# M706X.net
KiCad netlist of a schematic drawn in EAGLE
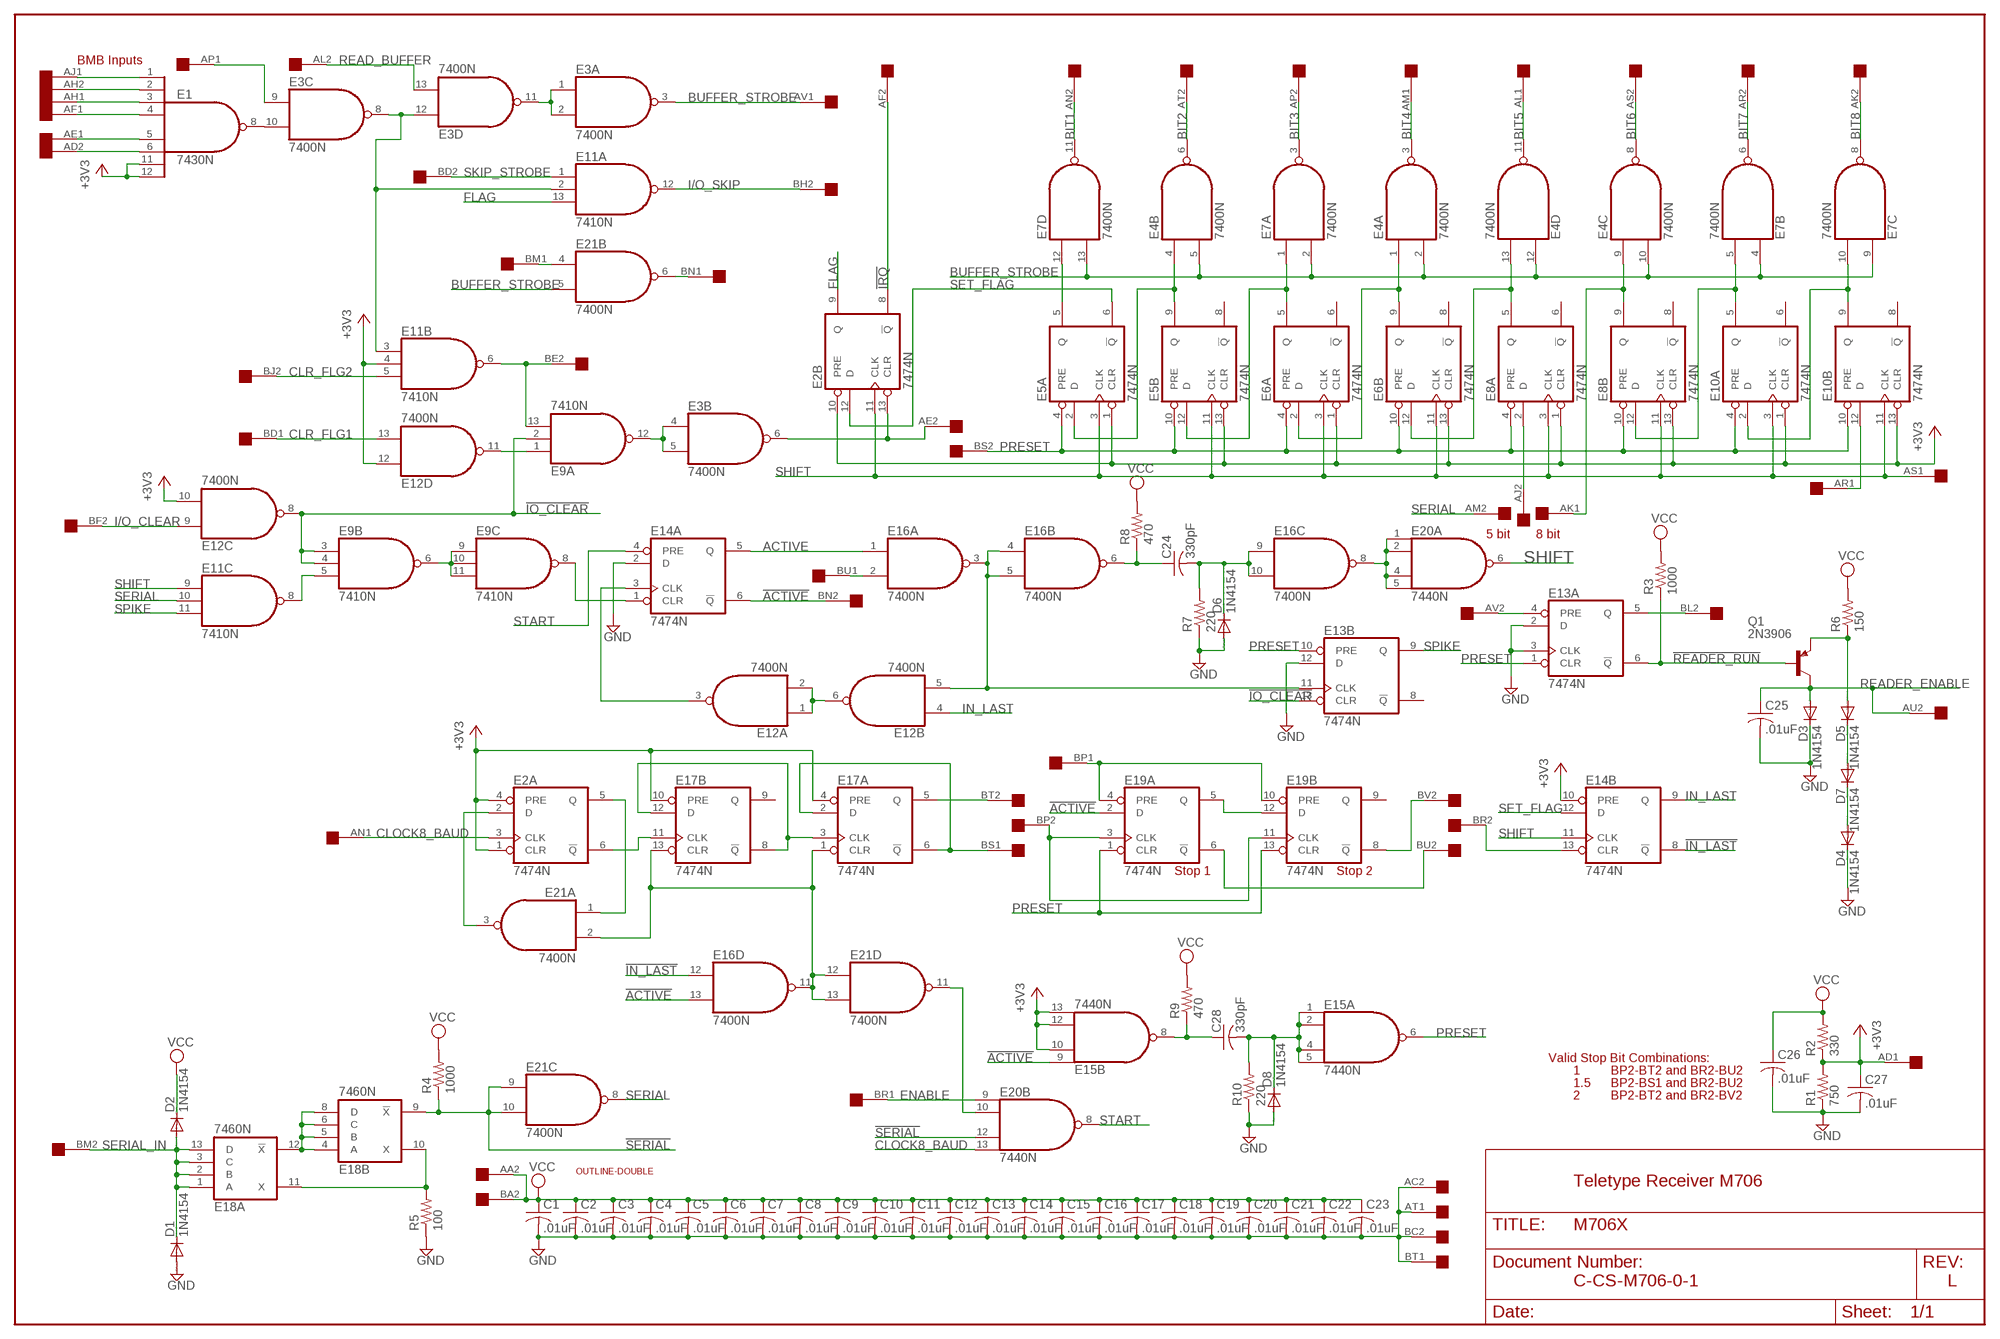
[diagram p0: schematic, sheet 1]

(export (version "E")
  (design (tool "Eeschema 10.0.6"))
  (components
    (comp (ref "C1")
      (value ".01uF")
      (footprint "eagle-import:C050-025X075")
      (libsource (lib "eagle-import") (part "C-US050-025X075"))
    )
    (comp (ref "C2")
      (value ".01uF")
      (footprint "eagle-import:C050-025X075")
      (libsource (lib "eagle-import") (part "C-US050-025X075"))
    )
    (comp (ref "C3")
      (value ".01uF")
      (footprint "eagle-import:C050-025X075")
      (libsource (lib "eagle-import") (part "C-US050-025X075"))
    )
    (comp (ref "C4")
      (value ".01uF")
      (footprint "eagle-import:C050-025X075")
      (libsource (lib "eagle-import") (part "C-US050-025X075"))
    )
    (comp (ref "C5")
      (value ".01uF")
      (footprint "eagle-import:C050-025X075")
      (libsource (lib "eagle-import") (part "C-US050-025X075"))
    )
    (comp (ref "C6")
      (value ".01uF")
      (footprint "eagle-import:C050-025X075")
      (libsource (lib "eagle-import") (part "C-US050-025X075"))
    )
    (comp (ref "C7")
      (value ".01uF")
      (footprint "eagle-import:C050-025X075")
      (libsource (lib "eagle-import") (part "C-US050-025X075"))
    )
    (comp (ref "C8")
      (value ".01uF")
      (footprint "eagle-import:C050-025X075")
      (libsource (lib "eagle-import") (part "C-US050-025X075"))
    )
    (comp (ref "C9")
      (value ".01uF")
      (footprint "eagle-import:C050-025X075")
      (libsource (lib "eagle-import") (part "C-US050-025X075"))
    )
    (comp (ref "C10")
      (value ".01uF")
      (footprint "eagle-import:C050-025X075")
      (libsource (lib "eagle-import") (part "C-US050-025X075"))
    )
    (comp (ref "C11")
      (value ".01uF")
      (footprint "eagle-import:C050-025X075")
      (libsource (lib "eagle-import") (part "C-US050-025X075"))
    )
    (comp (ref "C12")
      (value ".01uF")
      (footprint "eagle-import:C050-025X075")
      (libsource (lib "eagle-import") (part "C-US050-025X075"))
    )
    (comp (ref "C13")
      (value ".01uF")
      (footprint "eagle-import:C050-025X075")
      (libsource (lib "eagle-import") (part "C-US050-025X075"))
    )
    (comp (ref "C14")
      (value ".01uF")
      (footprint "eagle-import:C050-025X075")
      (libsource (lib "eagle-import") (part "C-US050-025X075"))
    )
    (comp (ref "C15")
      (value ".01uF")
      (footprint "eagle-import:C050-025X075")
      (libsource (lib "eagle-import") (part "C-US050-025X075"))
    )
    (comp (ref "C16")
      (value ".01uF")
      (footprint "eagle-import:C050-025X075")
      (libsource (lib "eagle-import") (part "C-US050-025X075"))
    )
    (comp (ref "C17")
      (value ".01uF")
      (footprint "eagle-import:C050-025X075")
      (libsource (lib "eagle-import") (part "C-US050-025X075"))
    )
    (comp (ref "C18")
      (value ".01uF")
      (footprint "eagle-import:C050-025X075")
      (libsource (lib "eagle-import") (part "C-US050-025X075"))
    )
    (comp (ref "C19")
      (value ".01uF")
      (footprint "eagle-import:C050-025X075")
      (libsource (lib "eagle-import") (part "C-US050-025X075"))
    )
    (comp (ref "C20")
      (value ".01uF")
      (footprint "eagle-import:C050-025X075")
      (libsource (lib "eagle-import") (part "C-US050-025X075"))
    )
    (comp (ref "C21")
      (value ".01uF")
      (footprint "eagle-import:C050-025X075")
      (libsource (lib "eagle-import") (part "C-US050-025X075"))
    )
    (comp (ref "C22")
      (value ".01uF")
      (footprint "eagle-import:C050-025X075")
      (libsource (lib "eagle-import") (part "C-US050-025X075"))
    )
    (comp (ref "C23")
      (value ".01uF")
      (footprint "eagle-import:C050-025X075")
      (libsource (lib "eagle-import") (part "C-US050-025X075"))
    )
    (comp (ref "C24")
      (value "330pF")
      (footprint "eagle-import:C050-025X075")
      (libsource (lib "eagle-import") (part "C-US050-025X075"))
    )
    (comp (ref "C25")
      (value ".01uF")
      (footprint "eagle-import:C050-025X075")
      (libsource (lib "eagle-import") (part "C-US050-025X075"))
    )
    (comp (ref "C26")
      (value ".01uF")
      (footprint "eagle-import:C050-025X075")
      (libsource (lib "eagle-import") (part "C-US050-025X075"))
    )
    (comp (ref "C27")
      (value ".01uF")
      (footprint "eagle-import:C050-025X075")
      (libsource (lib "eagle-import") (part "C-US050-025X075"))
    )
    (comp (ref "C28")
      (value "330pF")
      (footprint "eagle-import:C050-025X075")
      (libsource (lib "eagle-import") (part "C-US050-025X075"))
    )
    (comp (ref "D1")
      (value "1N4154")
      (footprint "eagle-import:DO35-10")
      (libsource (lib "eagle-import") (part "1N4148DO35-10"))
    )
    (comp (ref "D2")
      (value "1N4154")
      (footprint "eagle-import:DO35-10")
      (libsource (lib "eagle-import") (part "1N4148DO35-10"))
    )
    (comp (ref "D3")
      (value "1N4154")
      (footprint "eagle-import:DO35-10")
      (libsource (lib "eagle-import") (part "1N4148DO35-10"))
    )
    (comp (ref "D4")
      (value "1N4154")
      (footprint "eagle-import:DO35-10")
      (libsource (lib "eagle-import") (part "1N4148DO35-10"))
    )
    (comp (ref "D5")
      (value "1N4154")
      (footprint "eagle-import:DO35-10")
      (libsource (lib "eagle-import") (part "1N4148DO35-10"))
    )
    (comp (ref "D6")
      (value "1N4154")
      (footprint "eagle-import:DO35-10")
      (libsource (lib "eagle-import") (part "1N4148DO35-10"))
    )
    (comp (ref "D7")
      (value "1N4154")
      (footprint "eagle-import:DO35-10")
      (libsource (lib "eagle-import") (part "1N4148DO35-10"))
    )
    (comp (ref "D8")
      (value "1N4154")
      (footprint "eagle-import:DO35-10")
      (libsource (lib "eagle-import") (part "1N4148DO35-10"))
    )
    (comp (ref "E1")
      (value "7430N")
      (footprint "eagle-import:DIL14")
      (libsource (lib "eagle-import") (part "7430N"))
    )
    (comp (ref "E2")
      (value "7474N")
      (footprint "eagle-import:DIL14")
      (libsource (lib "eagle-import") (part "7474NS"))
    )
    (comp (ref "E3")
      (value "7400N")
      (footprint "eagle-import:DIL14")
      (libsource (lib "eagle-import") (part "7400N"))
    )
    (comp (ref "E4")
      (value "7400N")
      (footprint "eagle-import:DIL14")
      (libsource (lib "eagle-import") (part "7400N"))
    )
    (comp (ref "E5")
      (value "7474N")
      (footprint "eagle-import:DIL14")
      (libsource (lib "eagle-import") (part "7474NS"))
    )
    (comp (ref "E6")
      (value "7474N")
      (footprint "eagle-import:DIL14")
      (libsource (lib "eagle-import") (part "7474NS"))
    )
    (comp (ref "E7")
      (value "7400N")
      (footprint "eagle-import:DIL14")
      (libsource (lib "eagle-import") (part "7400N"))
    )
    (comp (ref "E8")
      (value "7474N")
      (footprint "eagle-import:DIL14")
      (libsource (lib "eagle-import") (part "7474NS"))
    )
    (comp (ref "E9")
      (value "7410N")
      (footprint "eagle-import:DIL14")
      (libsource (lib "eagle-import") (part "7410N"))
    )
    (comp (ref "E10")
      (value "7474N")
      (footprint "eagle-import:DIL14")
      (libsource (lib "eagle-import") (part "7474NS"))
    )
    (comp (ref "E11")
      (value "7410N")
      (footprint "eagle-import:DIL14")
      (libsource (lib "eagle-import") (part "7410N"))
    )
    (comp (ref "E12")
      (value "7400N")
      (footprint "eagle-import:DIL14")
      (libsource (lib "eagle-import") (part "7400N"))
    )
    (comp (ref "E13")
      (value "7474N")
      (footprint "eagle-import:DIL14")
      (libsource (lib "eagle-import") (part "7474NS"))
    )
    (comp (ref "E14")
      (value "7474N")
      (footprint "eagle-import:DIL14")
      (libsource (lib "eagle-import") (part "7474NS"))
    )
    (comp (ref "E15")
      (value "7440N")
      (footprint "eagle-import:DIL14")
      (libsource (lib "eagle-import") (part "7420NS"))
    )
    (comp (ref "E16")
      (value "7400N")
      (footprint "eagle-import:DIL14")
      (libsource (lib "eagle-import") (part "7400N"))
    )
    (comp (ref "E17")
      (value "7474N")
      (footprint "eagle-import:DIL14")
      (libsource (lib "eagle-import") (part "7474NS"))
    )
    (comp (ref "E18")
      (value "7460N")
      (footprint "eagle-import:DIL14")
      (libsource (lib "eagle-import") (part "7460N"))
    )
    (comp (ref "E19")
      (value "7474N")
      (footprint "eagle-import:DIL14")
      (libsource (lib "eagle-import") (part "7474NS"))
    )
    (comp (ref "E20")
      (value "7440N")
      (footprint "eagle-import:DIL14")
      (libsource (lib "eagle-import") (part "7420NS"))
    )
    (comp (ref "E21")
      (value "7400N")
      (footprint "eagle-import:DIL14")
      (libsource (lib "eagle-import") (part "7400N"))
    )
    (comp (ref "Q1")
      (value "2N3906")
      (footprint "eagle-import:TO39")
      (libsource (lib "eagle-import") (part "2N2904"))
    )
    (comp (ref "R1")
      (value "750")
      (footprint "eagle-import:0207_10")
      (libsource (lib "eagle-import") (part "R-US_0207/10"))
    )
    (comp (ref "R2")
      (value "330")
      (footprint "eagle-import:0207_10")
      (libsource (lib "eagle-import") (part "R-US_0207/10"))
    )
    (comp (ref "R3")
      (value "1000")
      (footprint "eagle-import:0207_10")
      (libsource (lib "eagle-import") (part "R-US_0207/10"))
    )
    (comp (ref "R4")
      (value "1000")
      (footprint "eagle-import:0207_10")
      (libsource (lib "eagle-import") (part "R-US_0207/10"))
    )
    (comp (ref "R5")
      (value "100")
      (footprint "eagle-import:0207_10")
      (libsource (lib "eagle-import") (part "R-US_0207/10"))
    )
    (comp (ref "R6")
      (value "150")
      (footprint "eagle-import:0207_10")
      (libsource (lib "eagle-import") (part "R-US_0207/10"))
    )
    (comp (ref "R7")
      (value "220")
      (footprint "eagle-import:0207_10")
      (libsource (lib "eagle-import") (part "R-US_0207/10"))
    )
    (comp (ref "R8")
      (value "470")
      (footprint "eagle-import:0207_10")
      (libsource (lib "eagle-import") (part "R-US_0207/10"))
    )
    (comp (ref "R9")
      (value "470")
      (footprint "eagle-import:0207_10")
      (libsource (lib "eagle-import") (part "R-US_0207/10"))
    )
    (comp (ref "R10")
      (value "220")
      (footprint "eagle-import:0207_10")
      (libsource (lib "eagle-import") (part "R-US_0207/10"))
    )
    (comp (ref "U$1")
      (value "OUTLINE-DOUBLE")
      (footprint "eagle-import:DOUBLE")
      (libsource (lib "eagle-import") (part "OUTLINE-DOUBLE"))
    )
    (comp (ref "U$2")
      (value "DOUBLE")
      (footprint "eagle-import:EDGE-CON4")
      (libsource (lib "eagle-import") (part "DOUBLE"))
    )
  )
  (nets
    (net (code "1") (name "+3V3") (class "Default")
      (node (ref "C27") (pin "1") (pinfunction "1_1") (pintype "passive"))
      (node (ref "E1") (pin "11") (pinfunction "I6_11") (pintype "input"))
      (node (ref "E1") (pin "12") (pinfunction "I7_12") (pintype "input"))
      (node (ref "E10") (pin "1") (pinfunction "CLR_1") (pintype "input"))
      (node (ref "E10") (pin "13") (pinfunction "CLR_13") (pintype "input"))
      (node (ref "E11") (pin "4") (pinfunction "I1_4") (pintype "input"))
      (node (ref "E12") (pin "10") (pinfunction "I1_10") (pintype "input"))
      (node (ref "E12") (pin "12") (pinfunction "I0_12") (pintype "input"))
      (node (ref "E14") (pin "10") (pinfunction "PRE_10") (pintype "input"))
      (node (ref "E15") (pin "10") (pinfunction "I1_10") (pintype "input"))
      (node (ref "E15") (pin "12") (pinfunction "I2_12") (pintype "input"))
      (node (ref "E15") (pin "13") (pinfunction "I3_13") (pintype "input"))
      (node (ref "E17") (pin "10") (pinfunction "PRE_10") (pintype "input"))
      (node (ref "E17") (pin "4") (pinfunction "PRE_4") (pintype "input"))
      (node (ref "E2") (pin "1") (pinfunction "CLR_1") (pintype "input"))
      (node (ref "E2") (pin "10") (pinfunction "PRE_10") (pintype "input"))
      (node (ref "E2") (pin "4") (pinfunction "PRE_4") (pintype "input"))
      (node (ref "E5") (pin "1") (pinfunction "CLR_1") (pintype "input"))
      (node (ref "E5") (pin "13") (pinfunction "CLR_13") (pintype "input"))
      (node (ref "E6") (pin "1") (pinfunction "CLR_1") (pintype "input"))
      (node (ref "E6") (pin "13") (pinfunction "CLR_13") (pintype "input"))
      (node (ref "E8") (pin "1") (pinfunction "CLR_1") (pintype "input"))
      (node (ref "E8") (pin "13") (pinfunction "CLR_13") (pintype "input"))
      (node (ref "R1") (pin "2") (pinfunction "2_2") (pintype "passive"))
      (node (ref "R2") (pin "1") (pinfunction "1_1") (pintype "passive"))
      (node (ref "U$2") (pin "AD1") (pinfunction "1_AD1") (pintype "bidirectional"))
    )
    (net (code "2") (name "/ACTIVE") (class "Default")
      (node (ref "E14") (pin "5") (pinfunction "Q_5") (pintype "output"))
      (node (ref "E16") (pin "1") (pinfunction "I0_1") (pintype "input"))
    )
    (net (code "3") (name "/BIT1") (class "Default")
      (node (ref "E7") (pin "11") (pinfunction "O_11") (pintype "output"))
      (node (ref "U$2") (pin "AN2") (pinfunction "1_AN2") (pintype "bidirectional"))
    )
    (net (code "4") (name "/BIT2") (class "Default")
      (node (ref "E4") (pin "6") (pinfunction "O_6") (pintype "output"))
      (node (ref "U$2") (pin "AT2") (pinfunction "1_AT2") (pintype "bidirectional"))
    )
    (net (code "5") (name "/BIT3") (class "Default")
      (node (ref "E7") (pin "3") (pinfunction "O_3") (pintype "output"))
      (node (ref "U$2") (pin "AP2") (pinfunction "1_AP2") (pintype "bidirectional"))
    )
    (net (code "6") (name "/BIT4") (class "Default")
      (node (ref "E4") (pin "3") (pinfunction "O_3") (pintype "output"))
      (node (ref "U$2") (pin "AM1") (pinfunction "1_AM1") (pintype "bidirectional"))
    )
    (net (code "7") (name "/BIT5") (class "Default")
      (node (ref "E4") (pin "11") (pinfunction "O_11") (pintype "output"))
      (node (ref "U$2") (pin "AL1") (pinfunction "1_AL1") (pintype "bidirectional"))
    )
    (net (code "8") (name "/BIT6") (class "Default")
      (node (ref "E4") (pin "8") (pinfunction "O_8") (pintype "output"))
      (node (ref "U$2") (pin "AS2") (pinfunction "1_AS2") (pintype "bidirectional"))
    )
    (net (code "9") (name "/BIT7") (class "Default")
      (node (ref "E7") (pin "6") (pinfunction "O_6") (pintype "output"))
      (node (ref "U$2") (pin "AR2") (pinfunction "1_AR2") (pintype "bidirectional"))
    )
    (net (code "10") (name "/BIT8") (class "Default")
      (node (ref "E7") (pin "8") (pinfunction "O_8") (pintype "output"))
      (node (ref "U$2") (pin "AK2") (pinfunction "1_AK2") (pintype "bidirectional"))
    )
    (net (code "11") (name "/BUFFER_STROBE") (class "Default")
      (node (ref "E21") (pin "5") (pinfunction "I1_5") (pintype "input"))
      (node (ref "E3") (pin "3") (pinfunction "O_3") (pintype "output"))
      (node (ref "E4") (pin "10") (pinfunction "I1_10") (pintype "input"))
      (node (ref "E4") (pin "12") (pinfunction "I0_12") (pintype "input"))
      (node (ref "E4") (pin "2") (pinfunction "I1_2") (pintype "input"))
      (node (ref "E4") (pin "5") (pinfunction "I1_5") (pintype "input"))
      (node (ref "E7") (pin "13") (pinfunction "I1_13") (pintype "input"))
      (node (ref "E7") (pin "2") (pinfunction "I1_2") (pintype "input"))
      (node (ref "E7") (pin "4") (pinfunction "I0_4") (pintype "input"))
      (node (ref "E7") (pin "9") (pinfunction "I0_9") (pintype "input"))
      (node (ref "U$2") (pin "AV1") (pinfunction "1_AV1") (pintype "bidirectional"))
    )
    (net (code "12") (name "/CLOCK8_BAUD") (class "Default")
      (node (ref "E2") (pin "3") (pinfunction "CLK_3") (pintype "input"))
      (node (ref "E20") (pin "13") (pinfunction "I3_13") (pintype "input"))
      (node (ref "U$2") (pin "AN1") (pinfunction "1_AN1") (pintype "bidirectional"))
    )
    (net (code "13") (name "/CLR_FLG1") (class "Default")
      (node (ref "E12") (pin "13") (pinfunction "I1_13") (pintype "input"))
      (node (ref "U$2") (pin "BD1") (pinfunction "1_BD1") (pintype "bidirectional"))
    )
    (net (code "14") (name "/CLR_FLG2") (class "Default")
      (node (ref "E11") (pin "5") (pinfunction "I2_5") (pintype "input"))
      (node (ref "U$2") (pin "BJ2") (pinfunction "1_BJ2") (pintype "bidirectional"))
    )
    (net (code "15") (name "/ENABLE") (class "Default")
      (node (ref "E20") (pin "9") (pinfunction "I0_9") (pintype "input"))
      (node (ref "U$2") (pin "BR1") (pinfunction "1_BR1") (pintype "bidirectional"))
    )
    (net (code "16") (name "/FLAG") (class "Default")
      (node (ref "E11") (pin "13") (pinfunction "I2_13") (pintype "input"))
      (node (ref "E2") (pin "9") (pinfunction "Q_9") (pintype "output"))
    )
    (net (code "17") (name "/IN_LAST") (class "Default")
      (node (ref "E12") (pin "4") (pinfunction "I0_4") (pintype "input"))
      (node (ref "E14") (pin "9") (pinfunction "Q_9") (pintype "output"))
    )
    (net (code "18") (name "/I{slash}O_CLEAR") (class "Default")
      (node (ref "E12") (pin "9") (pinfunction "I0_9") (pintype "input"))
      (node (ref "U$2") (pin "BF2") (pinfunction "1_BF2") (pintype "bidirectional"))
    )
    (net (code "19") (name "/I{slash}O_SKIP") (class "Default")
      (node (ref "E11") (pin "12") (pinfunction "O_12") (pintype "output"))
      (node (ref "U$2") (pin "BH2") (pinfunction "1_BH2") (pintype "bidirectional"))
    )
    (net (code "20") (name "/PRESET") (class "Default")
      (node (ref "E10") (pin "10") (pinfunction "PRE_10") (pintype "input"))
      (node (ref "E10") (pin "4") (pinfunction "PRE_4") (pintype "input"))
      (node (ref "E13") (pin "1") (pinfunction "CLR_1") (pintype "input"))
      (node (ref "E13") (pin "10") (pinfunction "PRE_10") (pintype "input"))
      (node (ref "E15") (pin "6") (pinfunction "O_6") (pintype "output"))
      (node (ref "E19") (pin "1") (pinfunction "CLR_1") (pintype "input"))
      (node (ref "E19") (pin "13") (pinfunction "CLR_13") (pintype "input"))
      (node (ref "E5") (pin "10") (pinfunction "PRE_10") (pintype "input"))
      (node (ref "E5") (pin "4") (pinfunction "PRE_4") (pintype "input"))
      (node (ref "E6") (pin "10") (pinfunction "PRE_10") (pintype "input"))
      (node (ref "E6") (pin "4") (pinfunction "PRE_4") (pintype "input"))
      (node (ref "E8") (pin "10") (pinfunction "PRE_10") (pintype "input"))
      (node (ref "E8") (pin "4") (pinfunction "PRE_4") (pintype "input"))
      (node (ref "U$2") (pin "BS2") (pinfunction "1_BS2") (pintype "bidirectional"))
    )
    (net (code "21") (name "/READER_ENABLE") (class "Default")
      (node (ref "C25") (pin "1") (pinfunction "1_1") (pintype "passive"))
      (node (ref "D3") (pin "A") (pinfunction "A_A") (pintype "passive"))
      (node (ref "Q1") (pin "3") (pinfunction "C_3") (pintype "passive"))
      (node (ref "U$2") (pin "AU2") (pinfunction "1_AU2") (pintype "bidirectional"))
    )
    (net (code "22") (name "/READ_BUFFER") (class "Default")
      (node (ref "E3") (pin "13") (pinfunction "I1_13") (pintype "input"))
      (node (ref "U$2") (pin "AL2") (pinfunction "1_AL2") (pintype "bidirectional"))
    )
    (net (code "23") (name "/SERIAL") (class "Default")
      (node (ref "E11") (pin "10") (pinfunction "I1_10") (pintype "input"))
      (node (ref "E21") (pin "8") (pinfunction "O_8") (pintype "output"))
      (node (ref "U$2") (pin "AM2") (pinfunction "1_AM2") (pintype "bidirectional"))
    )
    (net (code "24") (name "/SERIAL_IN") (class "Default")
      (node (ref "D1") (pin "C") (pinfunction "C_C") (pintype "passive"))
      (node (ref "D2") (pin "A") (pinfunction "A_A") (pintype "passive"))
      (node (ref "E18") (pin "1") (pinfunction "A_1") (pintype "input"))
      (node (ref "E18") (pin "13") (pinfunction "D_13") (pintype "input"))
      (node (ref "E18") (pin "2") (pinfunction "B_2") (pintype "input"))
      (node (ref "E18") (pin "3") (pinfunction "C_3") (pintype "input"))
      (node (ref "U$2") (pin "BM2") (pinfunction "1_BM2") (pintype "bidirectional"))
    )
    (net (code "25") (name "/SET_FLAG") (class "Default")
      (node (ref "E14") (pin "12") (pinfunction "D_12") (pintype "input"))
      (node (ref "E2") (pin "12") (pinfunction "D_12") (pintype "input"))
      (node (ref "E5") (pin "6") (pinfunction "~{Q}_6") (pintype "output"))
    )
    (net (code "26") (name "/SHIFT") (class "Default")
      (node (ref "E10") (pin "11") (pinfunction "CLK_11") (pintype "input"))
      (node (ref "E10") (pin "3") (pinfunction "CLK_3") (pintype "input"))
      (node (ref "E11") (pin "9") (pinfunction "I0_9") (pintype "input"))
      (node (ref "E14") (pin "11") (pinfunction "CLK_11") (pintype "input"))
      (node (ref "E2") (pin "11") (pinfunction "CLK_11") (pintype "input"))
      (node (ref "E20") (pin "6") (pinfunction "O_6") (pintype "output"))
      (node (ref "E5") (pin "11") (pinfunction "CLK_11") (pintype "input"))
      (node (ref "E5") (pin "3") (pinfunction "CLK_3") (pintype "input"))
      (node (ref "E6") (pin "11") (pinfunction "CLK_11") (pintype "input"))
      (node (ref "E6") (pin "3") (pinfunction "CLK_3") (pintype "input"))
      (node (ref "E8") (pin "11") (pinfunction "CLK_11") (pintype "input"))
      (node (ref "E8") (pin "3") (pinfunction "CLK_3") (pintype "input"))
      (node (ref "U$2") (pin "AS1") (pinfunction "1_AS1") (pintype "bidirectional"))
    )
    (net (code "27") (name "/SKIP_STROBE") (class "Default")
      (node (ref "E11") (pin "1") (pinfunction "I0_1") (pintype "input"))
      (node (ref "U$2") (pin "BD2") (pinfunction "1_BD2") (pintype "bidirectional"))
    )
    (net (code "28") (name "/SPIKE") (class "Default")
      (node (ref "E11") (pin "11") (pinfunction "I2_11") (pintype "input"))
      (node (ref "E13") (pin "9") (pinfunction "Q_9") (pintype "output"))
    )
    (net (code "29") (name "/START") (class "Default")
      (node (ref "E14") (pin "4") (pinfunction "PRE_4") (pintype "input"))
      (node (ref "E20") (pin "8") (pinfunction "O_8") (pintype "output"))
    )
    (net (code "30") (name "/~{ACTIVE}") (class "Default")
      (node (ref "E14") (pin "6") (pinfunction "~{Q}_6") (pintype "output"))
      (node (ref "E15") (pin "9") (pinfunction "I0_9") (pintype "input"))
      (node (ref "E16") (pin "13") (pinfunction "I1_13") (pintype "input"))
      (node (ref "E19") (pin "2") (pinfunction "D_2") (pintype "input"))
      (node (ref "U$2") (pin "BN2") (pinfunction "1_BN2") (pintype "bidirectional"))
    )
    (net (code "31") (name "/~{IN_LAST}") (class "Default")
      (node (ref "E14") (pin "8") (pinfunction "~{Q}_8") (pintype "output"))
      (node (ref "E16") (pin "12") (pinfunction "I0_12") (pintype "input"))
    )
    (net (code "32") (name "/~{IO_CLEAR}") (class "Default")
      (node (ref "E12") (pin "8") (pinfunction "O_8") (pintype "output"))
      (node (ref "E13") (pin "13") (pinfunction "CLR_13") (pintype "input"))
      (node (ref "E9") (pin "2") (pinfunction "I1_2") (pintype "input"))
      (node (ref "E9") (pin "3") (pinfunction "I0_3") (pintype "input"))
      (node (ref "E9") (pin "4") (pinfunction "I1_4") (pintype "input"))
    )
    (net (code "33") (name "/~{IRQ}") (class "Default")
      (node (ref "E2") (pin "8") (pinfunction "~{Q}_8") (pintype "output"))
      (node (ref "U$2") (pin "AF2") (pinfunction "1_AF2") (pintype "bidirectional"))
    )
    (net (code "34") (name "/~{READER_RUN}") (class "Default")
      (node (ref "E13") (pin "6") (pinfunction "~{Q}_6") (pintype "output"))
      (node (ref "Q1") (pin "2") (pinfunction "B_2") (pintype "passive"))
      (node (ref "R3") (pin "1") (pinfunction "1_1") (pintype "passive"))
    )
    (net (code "35") (name "/~{SERIAL}") (class "Default")
      (node (ref "E18") (pin "9") (pinfunction "~{X}_9") (pintype "output"))
      (node (ref "E20") (pin "12") (pinfunction "I2_12") (pintype "input"))
      (node (ref "E21") (pin "10") (pinfunction "I1_10") (pintype "input"))
      (node (ref "E21") (pin "9") (pinfunction "I0_9") (pintype "input"))
      (node (ref "R4") (pin "1") (pinfunction "1_1") (pintype "passive"))
    )
    (net (code "36") (name "GND") (class "Default")
      (node (ref "C1") (pin "2") (pinfunction "2_2") (pintype "passive"))
      (node (ref "C10") (pin "2") (pinfunction "2_2") (pintype "passive"))
      (node (ref "C11") (pin "2") (pinfunction "2_2") (pintype "passive"))
      (node (ref "C12") (pin "2") (pinfunction "2_2") (pintype "passive"))
      (node (ref "C13") (pin "2") (pinfunction "2_2") (pintype "passive"))
      (node (ref "C14") (pin "2") (pinfunction "2_2") (pintype "passive"))
      (node (ref "C15") (pin "2") (pinfunction "2_2") (pintype "passive"))
      (node (ref "C16") (pin "2") (pinfunction "2_2") (pintype "passive"))
      (node (ref "C17") (pin "2") (pinfunction "2_2") (pintype "passive"))
      (node (ref "C18") (pin "2") (pinfunction "2_2") (pintype "passive"))
      (node (ref "C19") (pin "2") (pinfunction "2_2") (pintype "passive"))
      (node (ref "C2") (pin "2") (pinfunction "2_2") (pintype "passive"))
      (node (ref "C20") (pin "2") (pinfunction "2_2") (pintype "passive"))
      (node (ref "C21") (pin "2") (pinfunction "2_2") (pintype "passive"))
      (node (ref "C22") (pin "2") (pinfunction "2_2") (pintype "passive"))
      (node (ref "C23") (pin "2") (pinfunction "2_2") (pintype "passive"))
      (node (ref "C25") (pin "2") (pinfunction "2_2") (pintype "passive"))
      (node (ref "C26") (pin "2") (pinfunction "2_2") (pintype "passive"))
      (node (ref "C27") (pin "2") (pinfunction "2_2") (pintype "passive"))
      (node (ref "C3") (pin "2") (pinfunction "2_2") (pintype "passive"))
      (node (ref "C4") (pin "2") (pinfunction "2_2") (pintype "passive"))
      (node (ref "C5") (pin "2") (pinfunction "2_2") (pintype "passive"))
      (node (ref "C6") (pin "2") (pinfunction "2_2") (pintype "passive"))
      (node (ref "C7") (pin "2") (pinfunction "2_2") (pintype "passive"))
      (node (ref "C8") (pin "2") (pinfunction "2_2") (pintype "passive"))
      (node (ref "C9") (pin "2") (pinfunction "2_2") (pintype "passive"))
      (node (ref "D1") (pin "A") (pinfunction "A_A") (pintype "passive"))
      (node (ref "D3") (pin "C") (pinfunction "C_C") (pintype "passive"))
      (node (ref "D4") (pin "C") (pinfunction "C_C") (pintype "passive"))
      (node (ref "D6") (pin "A") (pinfunction "A_A") (pintype "passive"))
      (node (ref "D8") (pin "A") (pinfunction "A_A") (pintype "passive"))
      (node (ref "E13") (pin "12") (pinfunction "D_12") (pintype "input"))
      (node (ref "E13") (pin "2") (pinfunction "D_2") (pintype "input"))
      (node (ref "E13") (pin "3") (pinfunction "CLK_3") (pintype "input"))
      (node (ref "E14") (pin "2") (pinfunction "D_2") (pintype "input"))
      (node (ref "R1") (pin "1") (pinfunction "1_1") (pintype "passive"))
      (node (ref "R10") (pin "1") (pinfunction "1_1") (pintype "passive"))
      (node (ref "R5") (pin "1") (pinfunction "1_1") (pintype "passive"))
      (node (ref "R7") (pin "1") (pinfunction "1_1") (pintype "passive"))
      (node (ref "U$2") (pin "AC2") (pinfunction "1_AC2") (pintype "bidirectional"))
      (node (ref "U$2") (pin "AT1") (pinfunction "1_AT1") (pintype "bidirectional"))
      (node (ref "U$2") (pin "BC2") (pinfunction "1_BC2") (pintype "bidirectional"))
      (node (ref "U$2") (pin "BT1") (pinfunction "1_BT1") (pintype "bidirectional"))
    )
    (net (code "37") (name "Net-(D4-PadA)") (class "Default")
      (node (ref "D4") (pin "A") (pinfunction "A_A") (pintype "passive"))
      (node (ref "D7") (pin "C") (pinfunction "C_C") (pintype "passive"))
    )
    (net (code "38") (name "Net-(D5-PadC)") (class "Default")
      (node (ref "D5") (pin "C") (pinfunction "C_C") (pintype "passive"))
      (node (ref "D7") (pin "A") (pinfunction "A_A") (pintype "passive"))
    )
    (net (code "39") (name "Net-(E1A-I0)") (class "Default")
      (node (ref "E1") (pin "1") (pinfunction "I0_1") (pintype "input"))
      (node (ref "U$2") (pin "AJ1") (pinfunction "1_AJ1") (pintype "bidirectional"))
    )
    (net (code "40") (name "Net-(E1A-I1)") (class "Default")
      (node (ref "E1") (pin "2") (pinfunction "I1_2") (pintype "input"))
      (node (ref "U$2") (pin "AH2") (pinfunction "1_AH2") (pintype "bidirectional"))
    )
    (net (code "41") (name "Net-(E1A-I2)") (class "Default")
      (node (ref "E1") (pin "3") (pinfunction "I2_3") (pintype "input"))
      (node (ref "U$2") (pin "AH1") (pinfunction "1_AH1") (pintype "bidirectional"))
    )
    (net (code "42") (name "Net-(E1A-I3)") (class "Default")
      (node (ref "E1") (pin "4") (pinfunction "I3_4") (pintype "input"))
      (node (ref "U$2") (pin "AF1") (pinfunction "1_AF1") (pintype "bidirectional"))
    )
    (net (code "43") (name "Net-(E1A-I4)") (class "Default")
      (node (ref "E1") (pin "5") (pinfunction "I4_5") (pintype "input"))
      (node (ref "U$2") (pin "AE1") (pinfunction "1_AE1") (pintype "bidirectional"))
    )
    (net (code "44") (name "Net-(E1A-I5)") (class "Default")
      (node (ref "E1") (pin "6") (pinfunction "I5_6") (pintype "input"))
      (node (ref "U$2") (pin "AD2") (pinfunction "1_AD2") (pintype "bidirectional"))
    )
    (net (code "45") (name "Net-(E1A-O)") (class "Default")
      (node (ref "E1") (pin "8") (pinfunction "O_8") (pintype "output"))
      (node (ref "E3") (pin "10") (pinfunction "I1_10") (pintype "input"))
    )
    (net (code "46") (name "Net-(E2B-CLR)") (class "Default")
      (node (ref "E2") (pin "13") (pinfunction "CLR_13") (pintype "input"))
      (node (ref "E3") (pin "6") (pinfunction "O_6") (pintype "output"))
      (node (ref "U$2") (pin "AE2") (pinfunction "1_AE2") (pintype "bidirectional"))
    )
    (net (code "47") (name "Net-(E3A-I0)") (class "Default")
      (node (ref "E3") (pin "1") (pinfunction "I0_1") (pintype "input"))
      (node (ref "E3") (pin "11") (pinfunction "O_11") (pintype "output"))
      (node (ref "E3") (pin "2") (pinfunction "I1_2") (pintype "input"))
    )
    (net (code "48") (name "Net-(E3B-I0)") (class "Default")
      (node (ref "E3") (pin "4") (pinfunction "I0_4") (pintype "input"))
      (node (ref "E3") (pin "5") (pinfunction "I1_5") (pintype "input"))
      (node (ref "E9") (pin "12") (pinfunction "O_12") (pintype "output"))
    )
    (net (code "49") (name "Net-(E3C-I0)") (class "Default")
      (node (ref "E3") (pin "9") (pinfunction "I0_9") (pintype "input"))
      (node (ref "U$2") (pin "AP1") (pinfunction "1_AP1") (pintype "bidirectional"))
    )
    (net (code "50") (name "Net-(E4A-I0)") (class "Default")
      (node (ref "E4") (pin "1") (pinfunction "I0_1") (pintype "input"))
      (node (ref "E6") (pin "2") (pinfunction "D_2") (pintype "input"))
      (node (ref "E6") (pin "9") (pinfunction "Q_9") (pintype "output"))
    )
    (net (code "51") (name "Net-(E4B-I0)") (class "Default")
      (node (ref "E4") (pin "4") (pinfunction "I0_4") (pintype "input"))
      (node (ref "E5") (pin "2") (pinfunction "D_2") (pintype "input"))
      (node (ref "E5") (pin "9") (pinfunction "Q_9") (pintype "output"))
    )
    (net (code "52") (name "Net-(E4C-I0)") (class "Default")
      (node (ref "E4") (pin "9") (pinfunction "I0_9") (pintype "input"))
      (node (ref "E8") (pin "9") (pinfunction "Q_9") (pintype "output"))
      (node (ref "U$2") (pin "AK1") (pinfunction "1_AK1") (pintype "bidirectional"))
    )
    (net (code "53") (name "Net-(E4D-I1)") (class "Default")
      (node (ref "E4") (pin "13") (pinfunction "I1_13") (pintype "input"))
      (node (ref "E6") (pin "12") (pinfunction "D_12") (pintype "input"))
      (node (ref "E8") (pin "5") (pinfunction "Q_5") (pintype "output"))
    )
    (net (code "54") (name "Net-(E5A-Q)") (class "Default")
      (node (ref "E5") (pin "5") (pinfunction "Q_5") (pintype "output"))
      (node (ref "E7") (pin "12") (pinfunction "I0_12") (pintype "input"))
    )
    (net (code "55") (name "Net-(E5B-D)") (class "Default")
      (node (ref "E5") (pin "12") (pinfunction "D_12") (pintype "input"))
      (node (ref "E6") (pin "5") (pinfunction "Q_5") (pintype "output"))
      (node (ref "E7") (pin "1") (pinfunction "I0_1") (pintype "input"))
    )
    (net (code "56") (name "Net-(E8A-D)") (class "Default")
      (node (ref "E8") (pin "2") (pinfunction "D_2") (pintype "input"))
      (node (ref "U$2") (pin "AJ2") (pinfunction "1_AJ2") (pintype "bidirectional"))
    )
    (net (code "57") (name "Net-(E9B-O)") (class "Default")
      (node (ref "E9") (pin "10") (pinfunction "I1_10") (pintype "input"))
      (node (ref "E9") (pin "11") (pinfunction "I2_11") (pintype "input"))
      (node (ref "E9") (pin "6") (pinfunction "O_6") (pintype "output"))
      (node (ref "E9") (pin "9") (pinfunction "I0_9") (pintype "input"))
    )
    (net (code "58") (name "Net-(E10A-D)") (class "Default")
      (node (ref "E10") (pin "2") (pinfunction "D_2") (pintype "input"))
      (node (ref "E10") (pin "9") (pinfunction "Q_9") (pintype "output"))
      (node (ref "E7") (pin "10") (pinfunction "I1_10") (pintype "input"))
    )
    (net (code "59") (name "Net-(E10A-Q)") (class "Default")
      (node (ref "E10") (pin "5") (pinfunction "Q_5") (pintype "output"))
      (node (ref "E7") (pin "5") (pinfunction "I1_5") (pintype "input"))
      (node (ref "E8") (pin "12") (pinfunction "D_12") (pintype "input"))
    )
    (net (code "60") (name "Net-(E10B-D)") (class "Default")
      (node (ref "E10") (pin "12") (pinfunction "D_12") (pintype "input"))
      (node (ref "U$2") (pin "AR1") (pinfunction "1_AR1") (pintype "bidirectional"))
    )
    (net (code "61") (name "Net-(E11A-I1)") (class "Default")
      (node (ref "E11") (pin "2") (pinfunction "I1_2") (pintype "input"))
      (node (ref "E11") (pin "3") (pinfunction "I0_3") (pintype "input"))
      (node (ref "E3") (pin "12") (pinfunction "I0_12") (pintype "input"))
      (node (ref "E3") (pin "8") (pinfunction "O_8") (pintype "output"))
    )
    (net (code "62") (name "Net-(E11B-O)") (class "Default")
      (node (ref "E11") (pin "6") (pinfunction "O_6") (pintype "output"))
      (node (ref "E9") (pin "13") (pinfunction "I2_13") (pintype "input"))
      (node (ref "U$2") (pin "BE2") (pinfunction "1_BE2") (pintype "bidirectional"))
    )
    (net (code "63") (name "Net-(E11C-O)") (class "Default")
      (node (ref "E11") (pin "8") (pinfunction "O_8") (pintype "output"))
      (node (ref "E9") (pin "5") (pinfunction "I2_5") (pintype "input"))
    )
    (net (code "64") (name "Net-(E12A-I0)") (class "Default")
      (node (ref "E12") (pin "1") (pinfunction "I0_1") (pintype "input"))
      (node (ref "E12") (pin "2") (pinfunction "I1_2") (pintype "input"))
      (node (ref "E12") (pin "6") (pinfunction "O_6") (pintype "output"))
    )
    (net (code "65") (name "Net-(E12A-O)") (class "Default")
      (node (ref "E12") (pin "3") (pinfunction "O_3") (pintype "output"))
      (node (ref "E14") (pin "3") (pinfunction "CLK_3") (pintype "input"))
    )
    (net (code "66") (name "Net-(E12B-I1)") (class "Default")
      (node (ref "E12") (pin "5") (pinfunction "I1_5") (pintype "input"))
      (node (ref "E13") (pin "11") (pinfunction "CLK_11") (pintype "input"))
      (node (ref "E16") (pin "3") (pinfunction "O_3") (pintype "output"))
      (node (ref "E16") (pin "4") (pinfunction "I0_4") (pintype "input"))
      (node (ref "E16") (pin "5") (pinfunction "I1_5") (pintype "input"))
    )
    (net (code "67") (name "Net-(E12D-O)") (class "Default")
      (node (ref "E12") (pin "11") (pinfunction "O_11") (pintype "output"))
      (node (ref "E9") (pin "1") (pinfunction "I0_1") (pintype "input"))
    )
    (net (code "68") (name "Net-(E13A-PRE)") (class "Default")
      (node (ref "E13") (pin "4") (pinfunction "PRE_4") (pintype "input"))
      (node (ref "U$2") (pin "AV2") (pinfunction "1_AV2") (pintype "bidirectional"))
    )
    (net (code "69") (name "Net-(E13A-Q)") (class "Default")
      (node (ref "E13") (pin "5") (pinfunction "Q_5") (pintype "output"))
      (node (ref "U$2") (pin "BL2") (pinfunction "1_BL2") (pintype "bidirectional"))
    )
    (net (code "70") (name "Net-(E14A-CLR)") (class "Default")
      (node (ref "E14") (pin "1") (pinfunction "CLR_1") (pintype "input"))
      (node (ref "E9") (pin "8") (pinfunction "O_8") (pintype "output"))
    )
    (net (code "71") (name "Net-(E14B-CLR)") (class "Default")
      (node (ref "E14") (pin "13") (pinfunction "CLR_13") (pintype "input"))
      (node (ref "U$2") (pin "BR2") (pinfunction "1_BR2") (pintype "bidirectional"))
    )
    (net (code "72") (name "Net-(E15A-I0)") (class "Default")
      (node (ref "C28") (pin "2") (pinfunction "2_2") (pintype "passive"))
      (node (ref "D8") (pin "C") (pinfunction "C_C") (pintype "passive"))
      (node (ref "E15") (pin "1") (pinfunction "I0_1") (pintype "input"))
      (node (ref "E15") (pin "2") (pinfunction "I1_2") (pintype "input"))
      (node (ref "E15") (pin "4") (pinfunction "I2_4") (pintype "input"))
      (node (ref "E15") (pin "5") (pinfunction "I3_5") (pintype "input"))
      (node (ref "R10") (pin "2") (pinfunction "2_2") (pintype "passive"))
    )
    (net (code "73") (name "Net-(E15B-O)") (class "Default")
      (node (ref "C28") (pin "1") (pinfunction "1_1") (pintype "passive"))
      (node (ref "E15") (pin "8") (pinfunction "O_8") (pintype "output"))
      (node (ref "R9") (pin "1") (pinfunction "1_1") (pintype "passive"))
    )
    (net (code "74") (name "Net-(E16A-I1)") (class "Default")
      (node (ref "E16") (pin "2") (pinfunction "I1_2") (pintype "input"))
      (node (ref "U$2") (pin "BU1") (pinfunction "1_BU1") (pintype "bidirectional"))
    )
    (net (code "75") (name "Net-(E16B-O)") (class "Default")
      (node (ref "C24") (pin "1") (pinfunction "1_1") (pintype "passive"))
      (node (ref "E16") (pin "6") (pinfunction "O_6") (pintype "output"))
      (node (ref "R8") (pin "1") (pinfunction "1_1") (pintype "passive"))
    )
    (net (code "76") (name "Net-(E16C-I0)") (class "Default")
      (node (ref "C24") (pin "2") (pinfunction "2_2") (pintype "passive"))
      (node (ref "D6") (pin "C") (pinfunction "C_C") (pintype "passive"))
      (node (ref "E16") (pin "10") (pinfunction "I1_10") (pintype "input"))
      (node (ref "E16") (pin "9") (pinfunction "I0_9") (pintype "input"))
      (node (ref "R7") (pin "2") (pinfunction "2_2") (pintype "passive"))
    )
    (net (code "77") (name "Net-(E16C-O)") (class "Default")
      (node (ref "E16") (pin "8") (pinfunction "O_8") (pintype "output"))
      (node (ref "E20") (pin "1") (pinfunction "I0_1") (pintype "input"))
      (node (ref "E20") (pin "2") (pinfunction "I1_2") (pintype "input"))
      (node (ref "E20") (pin "4") (pinfunction "I2_4") (pintype "input"))
      (node (ref "E20") (pin "5") (pinfunction "I3_5") (pintype "input"))
    )
    (net (code "78") (name "Net-(E16D-O)") (class "Default")
      (node (ref "E16") (pin "11") (pinfunction "O_11") (pintype "output"))
      (node (ref "E17") (pin "1") (pinfunction "CLR_1") (pintype "input"))
      (node (ref "E17") (pin "13") (pinfunction "CLR_13") (pintype "input"))
      (node (ref "E21") (pin "12") (pinfunction "I0_12") (pintype "input"))
      (node (ref "E21") (pin "13") (pinfunction "I1_13") (pintype "input"))
      (node (ref "E21") (pin "2") (pinfunction "I1_2") (pintype "input"))
    )
    (net (code "79") (name "Net-(E17A-CLK)") (class "Default")
      (node (ref "E17") (pin "12") (pinfunction "D_12") (pintype "input"))
      (node (ref "E17") (pin "3") (pinfunction "CLK_3") (pintype "input"))
      (node (ref "E17") (pin "8") (pinfunction "~{Q}_8") (pintype "output"))
    )
    (net (code "80") (name "Net-(E17A-D)") (class "Default")
      (node (ref "E17") (pin "2") (pinfunction "D_2") (pintype "input"))
      (node (ref "E17") (pin "6") (pinfunction "~{Q}_6") (pintype "output"))
      (node (ref "U$2") (pin "BS1") (pinfunction "1_BS1") (pintype "bidirectional"))
    )
    (net (code "81") (name "Net-(E17A-Q)") (class "Default")
      (node (ref "E17") (pin "5") (pinfunction "Q_5") (pintype "output"))
      (node (ref "U$2") (pin "BT2") (pinfunction "1_BT2") (pintype "bidirectional"))
    )
    (net (code "82") (name "Net-(E17B-CLK)") (class "Default")
      (node (ref "E17") (pin "11") (pinfunction "CLK_11") (pintype "input"))
      (node (ref "E2") (pin "6") (pinfunction "~{Q}_6") (pintype "output"))
    )
    (net (code "83") (name "Net-(E18A-X)") (class "Default")
      (node (ref "E18") (pin "10") (pinfunction "X_10") (pintype "output"))
      (node (ref "E18") (pin "11") (pinfunction "X_11") (pintype "output"))
      (node (ref "R5") (pin "2") (pinfunction "2_2") (pintype "passive"))
    )
    (net (code "84") (name "Net-(E18A-~{X})") (class "Default")
      (node (ref "E18") (pin "12") (pinfunction "~{X}_12") (pintype "output"))
      (node (ref "E18") (pin "4") (pinfunction "A_4") (pintype "input"))
      (node (ref "E18") (pin "5") (pinfunction "B_5") (pintype "input"))
      (node (ref "E18") (pin "6") (pinfunction "C_6") (pintype "input"))
      (node (ref "E18") (pin "8") (pinfunction "D_8") (pintype "input"))
    )
    (net (code "85") (name "Net-(E19A-CLK)") (class "Default")
      (node (ref "E19") (pin "11") (pinfunction "CLK_11") (pintype "input"))
      (node (ref "E19") (pin "3") (pinfunction "CLK_3") (pintype "input"))
      (node (ref "U$2") (pin "BP2") (pinfunction "1_BP2") (pintype "bidirectional"))
    )
    (net (code "86") (name "Net-(E19A-PRE)") (class "Default")
      (node (ref "E19") (pin "10") (pinfunction "PRE_10") (pintype "input"))
      (node (ref "E19") (pin "4") (pinfunction "PRE_4") (pintype "input"))
      (node (ref "U$2") (pin "BP1") (pinfunction "1_BP1") (pintype "bidirectional"))
    )
    (net (code "87") (name "Net-(E19A-Q)") (class "Default")
      (node (ref "E19") (pin "12") (pinfunction "D_12") (pintype "input"))
      (node (ref "E19") (pin "5") (pinfunction "Q_5") (pintype "output"))
    )
    (net (code "88") (name "Net-(E19A-~{Q})") (class "Default")
      (node (ref "E19") (pin "6") (pinfunction "~{Q}_6") (pintype "output"))
      (node (ref "U$2") (pin "BU2") (pinfunction "1_BU2") (pintype "bidirectional"))
    )
    (net (code "89") (name "Net-(E19B-~{Q})") (class "Default")
      (node (ref "E19") (pin "8") (pinfunction "~{Q}_8") (pintype "output"))
      (node (ref "U$2") (pin "BV2") (pinfunction "1_BV2") (pintype "bidirectional"))
    )
    (net (code "90") (name "Net-(E20B-I1)") (class "Default")
      (node (ref "E20") (pin "10") (pinfunction "I1_10") (pintype "input"))
      (node (ref "E21") (pin "11") (pinfunction "O_11") (pintype "output"))
    )
    (net (code "91") (name "Net-(E21A-I0)") (class "Default")
      (node (ref "E2") (pin "5") (pinfunction "Q_5") (pintype "output"))
      (node (ref "E21") (pin "1") (pinfunction "I0_1") (pintype "input"))
    )
    (net (code "92") (name "Net-(E21A-O)") (class "Default")
      (node (ref "E2") (pin "2") (pinfunction "D_2") (pintype "input"))
      (node (ref "E21") (pin "3") (pinfunction "O_3") (pintype "output"))
    )
    (net (code "93") (name "Net-(E21B-I0)") (class "Default")
      (node (ref "E21") (pin "4") (pinfunction "I0_4") (pintype "input"))
      (node (ref "U$2") (pin "BM1") (pinfunction "1_BM1") (pintype "bidirectional"))
    )
    (net (code "94") (name "Net-(E21B-O)") (class "Default")
      (node (ref "E21") (pin "6") (pinfunction "O_6") (pintype "output"))
      (node (ref "U$2") (pin "BN1") (pinfunction "1_BN1") (pintype "bidirectional"))
    )
    (net (code "95") (name "Net-(Q1-E)") (class "Default")
      (node (ref "D5") (pin "A") (pinfunction "A_A") (pintype "passive"))
      (node (ref "Q1") (pin "1") (pinfunction "E_1") (pintype "passive"))
      (node (ref "R6") (pin "1") (pinfunction "1_1") (pintype "passive"))
    )
    (net (code "96") (name "VCC") (class "Default")
      (node (ref "C1") (pin "1") (pinfunction "1_1") (pintype "passive"))
      (node (ref "C10") (pin "1") (pinfunction "1_1") (pintype "passive"))
      (node (ref "C11") (pin "1") (pinfunction "1_1") (pintype "passive"))
      (node (ref "C12") (pin "1") (pinfunction "1_1") (pintype "passive"))
      (node (ref "C13") (pin "1") (pinfunction "1_1") (pintype "passive"))
      (node (ref "C14") (pin "1") (pinfunction "1_1") (pintype "passive"))
      (node (ref "C15") (pin "1") (pinfunction "1_1") (pintype "passive"))
      (node (ref "C16") (pin "1") (pinfunction "1_1") (pintype "passive"))
      (node (ref "C17") (pin "1") (pinfunction "1_1") (pintype "passive"))
      (node (ref "C18") (pin "1") (pinfunction "1_1") (pintype "passive"))
      (node (ref "C19") (pin "1") (pinfunction "1_1") (pintype "passive"))
      (node (ref "C2") (pin "1") (pinfunction "1_1") (pintype "passive"))
      (node (ref "C20") (pin "1") (pinfunction "1_1") (pintype "passive"))
      (node (ref "C21") (pin "1") (pinfunction "1_1") (pintype "passive"))
      (node (ref "C22") (pin "1") (pinfunction "1_1") (pintype "passive"))
      (node (ref "C23") (pin "1") (pinfunction "1_1") (pintype "passive"))
      (node (ref "C26") (pin "1") (pinfunction "1_1") (pintype "passive"))
      (node (ref "C3") (pin "1") (pinfunction "1_1") (pintype "passive"))
      (node (ref "C4") (pin "1") (pinfunction "1_1") (pintype "passive"))
      (node (ref "C5") (pin "1") (pinfunction "1_1") (pintype "passive"))
      (node (ref "C6") (pin "1") (pinfunction "1_1") (pintype "passive"))
      (node (ref "C7") (pin "1") (pinfunction "1_1") (pintype "passive"))
      (node (ref "C8") (pin "1") (pinfunction "1_1") (pintype "passive"))
      (node (ref "C9") (pin "1") (pinfunction "1_1") (pintype "passive"))
      (node (ref "D2") (pin "C") (pinfunction "C_C") (pintype "passive"))
      (node (ref "R2") (pin "2") (pinfunction "2_2") (pintype "passive"))
      (node (ref "R3") (pin "2") (pinfunction "2_2") (pintype "passive"))
      (node (ref "R4") (pin "2") (pinfunction "2_2") (pintype "passive"))
      (node (ref "R6") (pin "2") (pinfunction "2_2") (pintype "passive"))
      (node (ref "R8") (pin "2") (pinfunction "2_2") (pintype "passive"))
      (node (ref "R9") (pin "2") (pinfunction "2_2") (pintype "passive"))
      (node (ref "U$2") (pin "AA2") (pinfunction "1_AA2") (pintype "bidirectional"))
      (node (ref "U$2") (pin "BA2") (pinfunction "1_BA2") (pintype "bidirectional"))
    )
    (net (code "97") (name "unconnected-(E5B-~{Q}-Pad8)") (class "Default")
      (node (ref "E5") (pin "8") (pinfunction "~{Q}_8") (pintype "output"))
    )
    (net (code "98") (name "unconnected-(E6A-~{Q}-Pad6)") (class "Default")
      (node (ref "E6") (pin "6") (pinfunction "~{Q}_6") (pintype "output"))
    )
    (net (code "99") (name "unconnected-(E6B-~{Q}-Pad8)") (class "Default")
      (node (ref "E6") (pin "8") (pinfunction "~{Q}_8") (pintype "output"))
    )
    (net (code "100") (name "unconnected-(E8A-~{Q}-Pad6)") (class "Default")
      (node (ref "E8") (pin "6") (pinfunction "~{Q}_6") (pintype "output"))
    )
    (net (code "101") (name "unconnected-(E8B-~{Q}-Pad8)") (class "Default")
      (node (ref "E8") (pin "8") (pinfunction "~{Q}_8") (pintype "output"))
    )
    (net (code "102") (name "unconnected-(E10A-~{Q}-Pad6)") (class "Default")
      (node (ref "E10") (pin "6") (pinfunction "~{Q}_6") (pintype "output"))
    )
    (net (code "103") (name "unconnected-(E10B-~{Q}-Pad8)") (class "Default")
      (node (ref "E10") (pin "8") (pinfunction "~{Q}_8") (pintype "output"))
    )
    (net (code "104") (name "unconnected-(E13B-~{Q}-Pad8)") (class "Default")
      (node (ref "E13") (pin "8") (pinfunction "~{Q}_8") (pintype "output"))
    )
    (net (code "105") (name "unconnected-(E17B-Q-Pad9)") (class "Default")
      (node (ref "E17") (pin "9") (pinfunction "Q_9") (pintype "output"))
    )
    (net (code "106") (name "unconnected-(E19B-Q-Pad9)") (class "Default")
      (node (ref "E19") (pin "9") (pinfunction "Q_9") (pintype "output"))
    )
  )
)
